# house_rev2.net
KiCad netlist of a schematic drawn in EAGLE
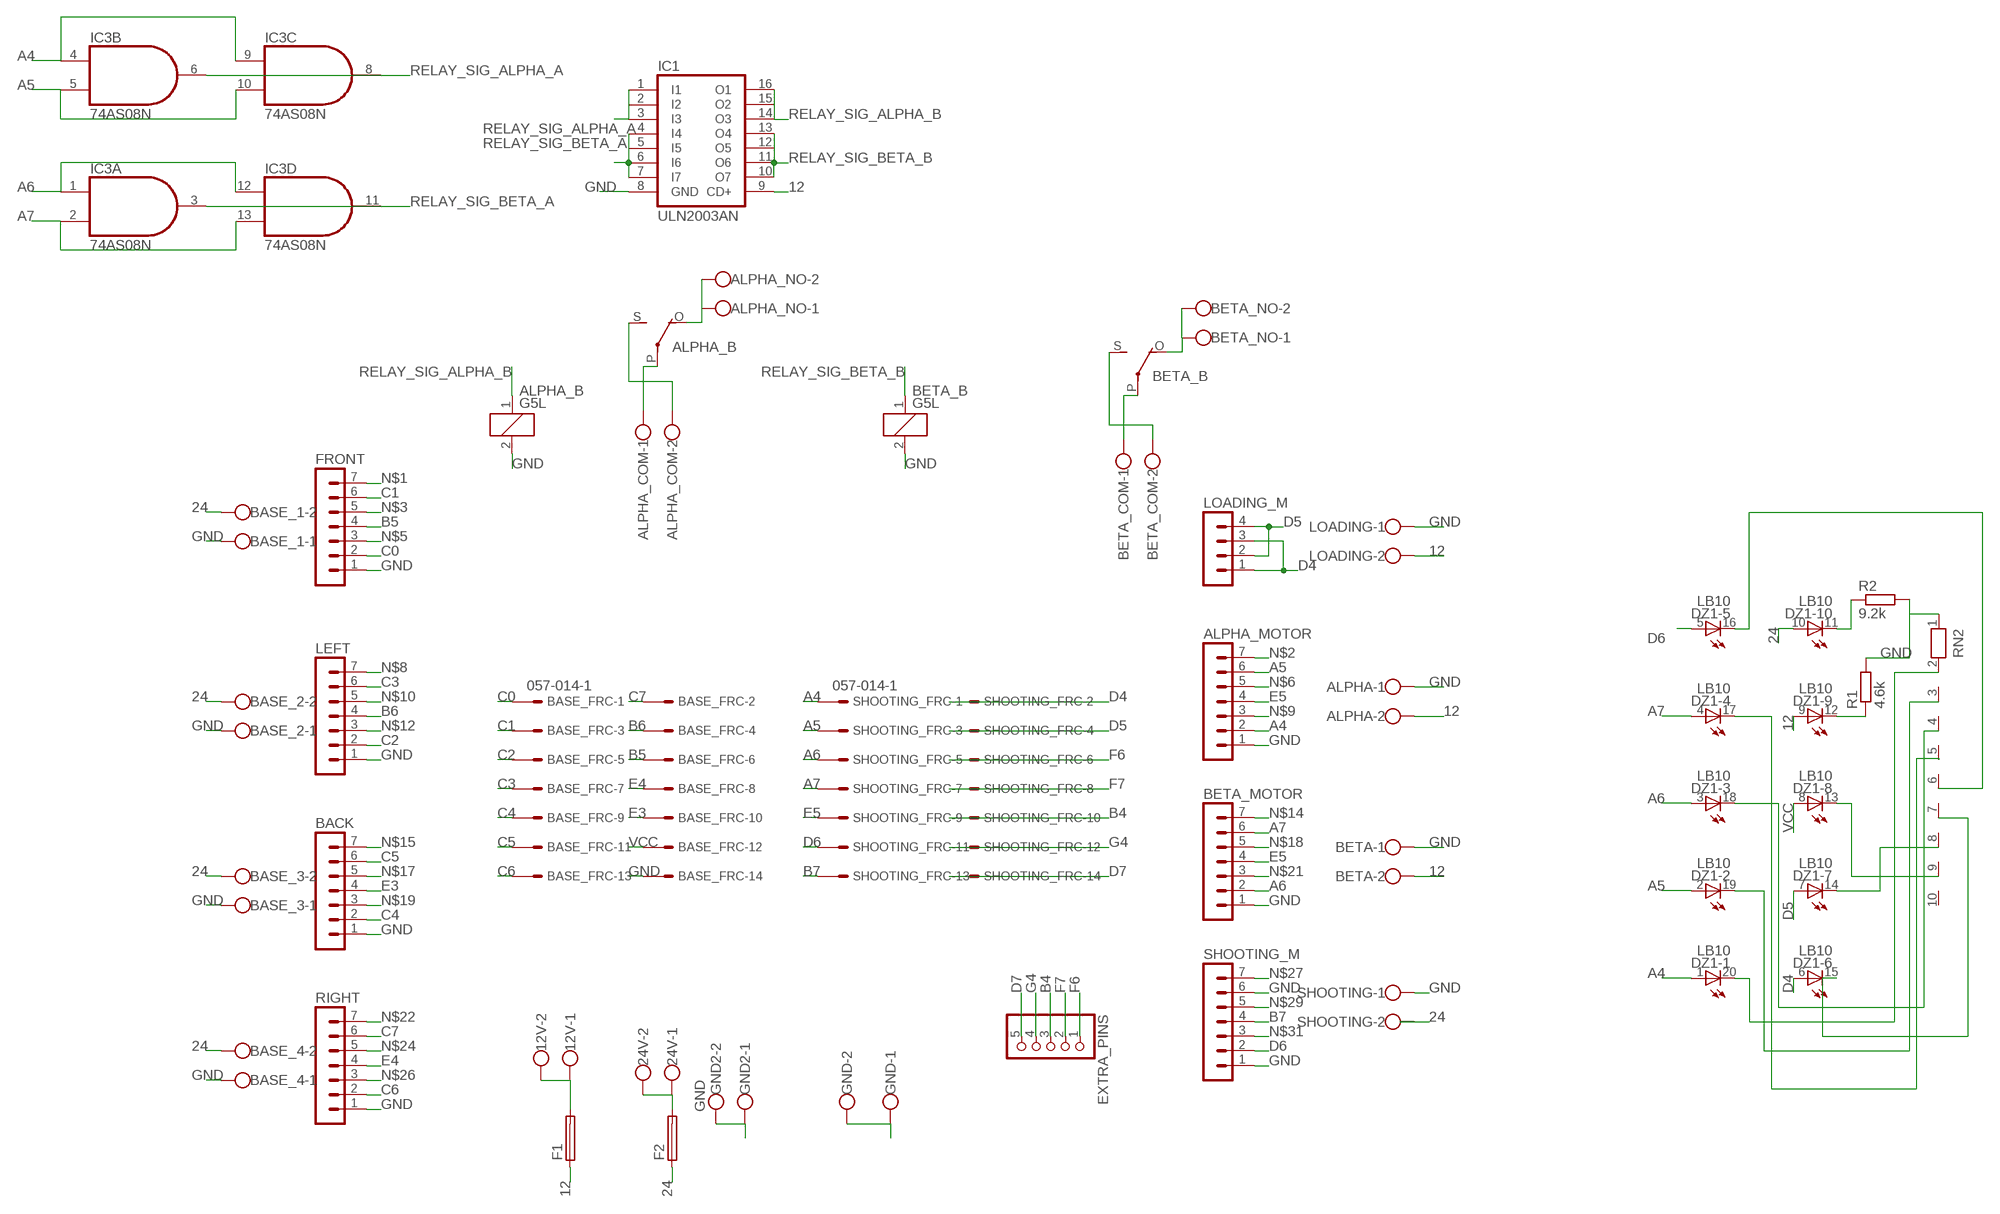
[diagram p0: schematic, sheet 1]

(export (version "E")
  (design (tool "Eeschema 10.0.6"))
  (components
    (comp (ref "12V")
      (value "W237-102")
      (footprint "eagle-import:W237-102")
      (fields (field (name "MPN") "237-102"))
      (libsource (lib "eagle-import") (part "W237-102"))
    )
    (comp (ref "24V")
      (value "W237-102")
      (footprint "eagle-import:W237-102")
      (fields (field (name "MPN") "237-102"))
      (libsource (lib "eagle-import") (part "W237-102"))
    )
    (comp (ref "ALPHA")
      (value "W237-102")
      (footprint "eagle-import:W237-102")
      (fields (field (name "MPN") "237-102"))
      (libsource (lib "eagle-import") (part "W237-102"))
    )
    (comp (ref "ALPHA_B")
      (value "G5L")
      (footprint "eagle-import:G5LE")
      (libsource (lib "eagle-import") (part "G5L"))
    )
    (comp (ref "ALPHA_COM")
      (value "W237-102")
      (footprint "eagle-import:W237-102")
      (fields (field (name "MPN") "237-102"))
      (libsource (lib "eagle-import") (part "W237-102"))
    )
    (comp (ref "ALPHA_MOTOR")
      (value "MA07-1")
      (footprint "eagle-import:MA07-1")
      (libsource (lib "eagle-import") (part "MA07-1"))
    )
    (comp (ref "ALPHA_NO")
      (value "W237-102")
      (footprint "eagle-import:W237-102")
      (fields (field (name "MPN") "237-102"))
      (libsource (lib "eagle-import") (part "W237-102"))
    )
    (comp (ref "BACK")
      (value "MA07-1")
      (footprint "eagle-import:MA07-1")
      (libsource (lib "eagle-import") (part "MA07-1"))
    )
    (comp (ref "BASE_1")
      (value "W237-102")
      (footprint "eagle-import:W237-102")
      (fields (field (name "MPN") "237-102"))
      (libsource (lib "eagle-import") (part "W237-102"))
    )
    (comp (ref "BASE_2")
      (value "W237-102")
      (footprint "eagle-import:W237-102")
      (fields (field (name "MPN") "237-102"))
      (libsource (lib "eagle-import") (part "W237-102"))
    )
    (comp (ref "BASE_3")
      (value "W237-102")
      (footprint "eagle-import:W237-102")
      (fields (field (name "MPN") "237-102"))
      (libsource (lib "eagle-import") (part "W237-102"))
    )
    (comp (ref "BASE_4")
      (value "W237-102")
      (footprint "eagle-import:W237-102")
      (fields (field (name "MPN") "237-102"))
      (libsource (lib "eagle-import") (part "W237-102"))
    )
    (comp (ref "BASE_FRC")
      (value "057-014-1")
      (footprint "eagle-import:057-014-1")
      (libsource (lib "eagle-import") (part "057-014-1"))
    )
    (comp (ref "BETA")
      (value "W237-102")
      (footprint "eagle-import:W237-102")
      (fields (field (name "MPN") "237-102"))
      (libsource (lib "eagle-import") (part "W237-102"))
    )
    (comp (ref "BETA_B")
      (value "G5L")
      (footprint "eagle-import:G5LE")
      (libsource (lib "eagle-import") (part "G5L"))
    )
    (comp (ref "BETA_COM")
      (value "W237-102")
      (footprint "eagle-import:W237-102")
      (fields (field (name "MPN") "237-102"))
      (libsource (lib "eagle-import") (part "W237-102"))
    )
    (comp (ref "BETA_MOTOR")
      (value "MA07-1")
      (footprint "eagle-import:MA07-1")
      (libsource (lib "eagle-import") (part "MA07-1"))
    )
    (comp (ref "BETA_NO")
      (value "W237-102")
      (footprint "eagle-import:W237-102")
      (fields (field (name "MPN") "237-102"))
      (libsource (lib "eagle-import") (part "W237-102"))
    )
    (comp (ref "DZ1")
      (value "LB10")
      (footprint "eagle-import:LB10")
      (libsource (lib "eagle-import") (part "LB10"))
    )
    (comp (ref "EXTRA_PINS")
      (value "PINHD-1X5")
      (footprint "eagle-import:1X05")
      (libsource (lib "eagle-import") (part "PINHD-1X5"))
    )
    (comp (ref "F1")
      (value "SH25")
      (footprint "eagle-import:SH25")
      (fields (field (name "MF") "SCHURTER") (field (name "MPN") "0031.8211"))
      (libsource (lib "eagle-import") (part "SH25"))
    )
    (comp (ref "F2")
      (value "SH25")
      (footprint "eagle-import:SH25")
      (fields (field (name "MF") "SCHURTER") (field (name "MPN") "0031.8211"))
      (libsource (lib "eagle-import") (part "SH25"))
    )
    (comp (ref "FRONT")
      (value "MA07-1")
      (footprint "eagle-import:MA07-1")
      (libsource (lib "eagle-import") (part "MA07-1"))
    )
    (comp (ref "GND")
      (value "W237-102")
      (footprint "eagle-import:W237-102")
      (fields (field (name "MPN") "237-102"))
      (libsource (lib "eagle-import") (part "W237-102"))
    )
    (comp (ref "GND2")
      (value "GND")
      (footprint "eagle-import:W237-102")
      (fields (field (name "MPN") "237-102"))
      (libsource (lib "eagle-import") (part "W237-102"))
    )
    (comp (ref "IC1")
      (value "ULN2003AN")
      (footprint "eagle-import:DIL16")
      (libsource (lib "eagle-import") (part "ULN2003AN"))
    )
    (comp (ref "IC3")
      (value "74AS08N")
      (footprint "eagle-import:DIL14")
      (libsource (lib "eagle-import") (part "7408NAS"))
    )
    (comp (ref "LEFT")
      (value "MA07-1")
      (footprint "eagle-import:MA07-1")
      (libsource (lib "eagle-import") (part "MA07-1"))
    )
    (comp (ref "LOADING")
      (value "W237-102")
      (footprint "eagle-import:W237-102")
      (fields (field (name "MPN") "237-102"))
      (libsource (lib "eagle-import") (part "W237-102"))
    )
    (comp (ref "LOADING_M")
      (value "MA04-1")
      (footprint "eagle-import:MA04-1")
      (libsource (lib "eagle-import") (part "MA04-1"))
    )
    (comp (ref "R1")
      (value "4.6k")
      (footprint "eagle-import:0204_7")
      (libsource (lib "eagle-import") (part "R-EU_0204/7"))
    )
    (comp (ref "R2")
      (value "9.2k")
      (footprint "eagle-import:0204_7")
      (libsource (lib "eagle-import") (part "R-EU_0204/7"))
    )
    (comp (ref "RIGHT")
      (value "MA07-1")
      (footprint "eagle-import:MA07-1")
      (libsource (lib "eagle-import") (part "MA07-1"))
    )
    (comp (ref "RN2")
      (value "RN09")
      (footprint "eagle-import:RN-10")
      (libsource (lib "eagle-import") (part "RN09"))
    )
    (comp (ref "SHOOTING")
      (value "W237-102")
      (footprint "eagle-import:W237-102")
      (fields (field (name "MPN") "237-102"))
      (libsource (lib "eagle-import") (part "W237-102"))
    )
    (comp (ref "SHOOTING_FRC")
      (value "057-014-1")
      (footprint "eagle-import:057-014-1")
      (libsource (lib "eagle-import") (part "057-014-1"))
    )
    (comp (ref "SHOOTING_M")
      (value "MA07-1")
      (footprint "eagle-import:MA07-1")
      (libsource (lib "eagle-import") (part "MA07-1"))
    )
  )
  (nets
    (net (code "1") (name "/12") (class "Default")
      (node (ref "ALPHA") (pin "2") (pinfunction "KL_2") (pintype "passive"))
      (node (ref "BETA") (pin "2") (pinfunction "KL_2") (pintype "passive"))
      (node (ref "DZ1") (pin "9") (pinfunction "A_9") (pintype "passive"))
      (node (ref "F1") (pin "1") (pinfunction "1_1") (pintype "passive"))
      (node (ref "IC1") (pin "9") (pinfunction "CD+_9") (pintype "passive"))
      (node (ref "LOADING") (pin "2") (pinfunction "KL_2") (pintype "passive"))
    )
    (net (code "2") (name "/24") (class "Default")
      (node (ref "BASE_1") (pin "2") (pinfunction "KL_2") (pintype "passive"))
      (node (ref "BASE_2") (pin "2") (pinfunction "KL_2") (pintype "passive"))
      (node (ref "BASE_3") (pin "2") (pinfunction "KL_2") (pintype "passive"))
      (node (ref "BASE_4") (pin "2") (pinfunction "KL_2") (pintype "passive"))
      (node (ref "DZ1") (pin "10") (pinfunction "A_10") (pintype "passive"))
      (node (ref "F2") (pin "1") (pinfunction "1_1") (pintype "passive"))
      (node (ref "SHOOTING") (pin "2") (pinfunction "KL_2") (pintype "passive"))
    )
    (net (code "3") (name "/A4") (class "Default")
      (node (ref "ALPHA_MOTOR") (pin "2") (pinfunction "2_2") (pintype "passive"))
      (node (ref "DZ1") (pin "1") (pinfunction "A_1") (pintype "passive"))
      (node (ref "IC3") (pin "4") (pinfunction "I0_4") (pintype "input"))
      (node (ref "IC3") (pin "9") (pinfunction "I0_9") (pintype "input"))
      (node (ref "SHOOTING_FRC") (pin "1") (pinfunction "S_1") (pintype "passive"))
    )
    (net (code "4") (name "/A5") (class "Default")
      (node (ref "ALPHA_MOTOR") (pin "6") (pinfunction "6_6") (pintype "passive"))
      (node (ref "DZ1") (pin "2") (pinfunction "A_2") (pintype "passive"))
      (node (ref "IC3") (pin "10") (pinfunction "I1_10") (pintype "input"))
      (node (ref "IC3") (pin "5") (pinfunction "I1_5") (pintype "input"))
      (node (ref "SHOOTING_FRC") (pin "3") (pinfunction "S_3") (pintype "passive"))
    )
    (net (code "5") (name "/A6") (class "Default")
      (node (ref "BETA_MOTOR") (pin "2") (pinfunction "2_2") (pintype "passive"))
      (node (ref "DZ1") (pin "3") (pinfunction "A_3") (pintype "passive"))
      (node (ref "IC3") (pin "1") (pinfunction "I0_1") (pintype "input"))
      (node (ref "IC3") (pin "12") (pinfunction "I0_12") (pintype "input"))
      (node (ref "SHOOTING_FRC") (pin "5") (pinfunction "S_5") (pintype "passive"))
    )
    (net (code "6") (name "/A7") (class "Default")
      (node (ref "BETA_MOTOR") (pin "6") (pinfunction "6_6") (pintype "passive"))
      (node (ref "DZ1") (pin "4") (pinfunction "A_4") (pintype "passive"))
      (node (ref "IC3") (pin "13") (pinfunction "I1_13") (pintype "input"))
      (node (ref "IC3") (pin "2") (pinfunction "I1_2") (pintype "input"))
      (node (ref "SHOOTING_FRC") (pin "7") (pinfunction "S_7") (pintype "passive"))
    )
    (net (code "7") (name "/B4") (class "Default")
      (node (ref "EXTRA_PINS") (pin "3") (pinfunction "3_3") (pintype "passive"))
      (node (ref "SHOOTING_FRC") (pin "10") (pinfunction "S_10") (pintype "passive"))
    )
    (net (code "8") (name "/B5") (class "Default")
      (node (ref "BASE_FRC") (pin "6") (pinfunction "S_6") (pintype "passive"))
      (node (ref "FRONT") (pin "4") (pinfunction "4_4") (pintype "passive"))
    )
    (net (code "9") (name "/B6") (class "Default")
      (node (ref "BASE_FRC") (pin "4") (pinfunction "S_4") (pintype "passive"))
      (node (ref "LEFT") (pin "4") (pinfunction "4_4") (pintype "passive"))
    )
    (net (code "10") (name "/B7") (class "Default")
      (node (ref "SHOOTING_FRC") (pin "13") (pinfunction "S_13") (pintype "passive"))
      (node (ref "SHOOTING_M") (pin "4") (pinfunction "4_4") (pintype "passive"))
    )
    (net (code "11") (name "/C0") (class "Default")
      (node (ref "BASE_FRC") (pin "1") (pinfunction "S_1") (pintype "passive"))
      (node (ref "FRONT") (pin "2") (pinfunction "2_2") (pintype "passive"))
    )
    (net (code "12") (name "/C1") (class "Default")
      (node (ref "BASE_FRC") (pin "3") (pinfunction "S_3") (pintype "passive"))
      (node (ref "FRONT") (pin "6") (pinfunction "6_6") (pintype "passive"))
    )
    (net (code "13") (name "/C2") (class "Default")
      (node (ref "BASE_FRC") (pin "5") (pinfunction "S_5") (pintype "passive"))
      (node (ref "LEFT") (pin "2") (pinfunction "2_2") (pintype "passive"))
    )
    (net (code "14") (name "/C3") (class "Default")
      (node (ref "BASE_FRC") (pin "7") (pinfunction "S_7") (pintype "passive"))
      (node (ref "LEFT") (pin "6") (pinfunction "6_6") (pintype "passive"))
    )
    (net (code "15") (name "/C4") (class "Default")
      (node (ref "BACK") (pin "2") (pinfunction "2_2") (pintype "passive"))
      (node (ref "BASE_FRC") (pin "9") (pinfunction "S_9") (pintype "passive"))
    )
    (net (code "16") (name "/C5") (class "Default")
      (node (ref "BACK") (pin "6") (pinfunction "6_6") (pintype "passive"))
      (node (ref "BASE_FRC") (pin "11") (pinfunction "S_11") (pintype "passive"))
    )
    (net (code "17") (name "/C6") (class "Default")
      (node (ref "BASE_FRC") (pin "13") (pinfunction "S_13") (pintype "passive"))
      (node (ref "RIGHT") (pin "2") (pinfunction "2_2") (pintype "passive"))
    )
    (net (code "18") (name "/C7") (class "Default")
      (node (ref "BASE_FRC") (pin "2") (pinfunction "S_2") (pintype "passive"))
      (node (ref "RIGHT") (pin "6") (pinfunction "6_6") (pintype "passive"))
    )
    (net (code "19") (name "/D4") (class "Default")
      (node (ref "DZ1") (pin "6") (pinfunction "A_6") (pintype "passive"))
      (node (ref "LOADING_M") (pin "1") (pinfunction "1_1") (pintype "passive"))
      (node (ref "LOADING_M") (pin "3") (pinfunction "3_3") (pintype "passive"))
      (node (ref "SHOOTING_FRC") (pin "2") (pinfunction "S_2") (pintype "passive"))
    )
    (net (code "20") (name "/D5") (class "Default")
      (node (ref "DZ1") (pin "7") (pinfunction "A_7") (pintype "passive"))
      (node (ref "LOADING_M") (pin "2") (pinfunction "2_2") (pintype "passive"))
      (node (ref "LOADING_M") (pin "4") (pinfunction "4_4") (pintype "passive"))
      (node (ref "SHOOTING_FRC") (pin "4") (pinfunction "S_4") (pintype "passive"))
    )
    (net (code "21") (name "/D6") (class "Default")
      (node (ref "DZ1") (pin "5") (pinfunction "A_5") (pintype "passive"))
      (node (ref "SHOOTING_FRC") (pin "11") (pinfunction "S_11") (pintype "passive"))
      (node (ref "SHOOTING_M") (pin "2") (pinfunction "2_2") (pintype "passive"))
    )
    (net (code "22") (name "/D7") (class "Default")
      (node (ref "EXTRA_PINS") (pin "5") (pinfunction "5_5") (pintype "passive"))
      (node (ref "SHOOTING_FRC") (pin "14") (pinfunction "S_14") (pintype "passive"))
    )
    (net (code "23") (name "/E3") (class "Default")
      (node (ref "BACK") (pin "4") (pinfunction "4_4") (pintype "passive"))
      (node (ref "BASE_FRC") (pin "10") (pinfunction "S_10") (pintype "passive"))
    )
    (net (code "24") (name "/E4") (class "Default")
      (node (ref "BASE_FRC") (pin "8") (pinfunction "S_8") (pintype "passive"))
      (node (ref "RIGHT") (pin "4") (pinfunction "4_4") (pintype "passive"))
    )
    (net (code "25") (name "/E5") (class "Default")
      (node (ref "ALPHA_MOTOR") (pin "4") (pinfunction "4_4") (pintype "passive"))
      (node (ref "BETA_MOTOR") (pin "4") (pinfunction "4_4") (pintype "passive"))
      (node (ref "SHOOTING_FRC") (pin "9") (pinfunction "S_9") (pintype "passive"))
    )
    (net (code "26") (name "/F6") (class "Default")
      (node (ref "EXTRA_PINS") (pin "1") (pinfunction "1_1") (pintype "passive"))
      (node (ref "SHOOTING_FRC") (pin "6") (pinfunction "S_6") (pintype "passive"))
    )
    (net (code "27") (name "/F7") (class "Default")
      (node (ref "EXTRA_PINS") (pin "2") (pinfunction "2_2") (pintype "passive"))
      (node (ref "SHOOTING_FRC") (pin "8") (pinfunction "S_8") (pintype "passive"))
    )
    (net (code "28") (name "/G4") (class "Default")
      (node (ref "EXTRA_PINS") (pin "4") (pinfunction "4_4") (pintype "passive"))
      (node (ref "SHOOTING_FRC") (pin "12") (pinfunction "S_12") (pintype "passive"))
    )
    (net (code "29") (name "/GND") (class "Default")
      (node (ref "ALPHA") (pin "1") (pinfunction "KL_1") (pintype "passive"))
      (node (ref "ALPHA_B") (pin "2") (pinfunction "2_2") (pintype "passive"))
      (node (ref "ALPHA_MOTOR") (pin "1") (pinfunction "1_1") (pintype "passive"))
      (node (ref "BACK") (pin "1") (pinfunction "1_1") (pintype "passive"))
      (node (ref "BASE_1") (pin "1") (pinfunction "KL_1") (pintype "passive"))
      (node (ref "BASE_2") (pin "1") (pinfunction "KL_1") (pintype "passive"))
      (node (ref "BASE_3") (pin "1") (pinfunction "KL_1") (pintype "passive"))
      (node (ref "BASE_4") (pin "1") (pinfunction "KL_1") (pintype "passive"))
      (node (ref "BASE_FRC") (pin "14") (pinfunction "S_14") (pintype "passive"))
      (node (ref "BETA") (pin "1") (pinfunction "KL_1") (pintype "passive"))
      (node (ref "BETA_B") (pin "2") (pinfunction "2_2") (pintype "passive"))
      (node (ref "BETA_MOTOR") (pin "1") (pinfunction "1_1") (pintype "passive"))
      (node (ref "FRONT") (pin "1") (pinfunction "1_1") (pintype "passive"))
      (node (ref "GND") (pin "1") (pinfunction "KL_1") (pintype "passive"))
      (node (ref "GND") (pin "2") (pinfunction "KL_2") (pintype "passive"))
      (node (ref "GND2") (pin "1") (pinfunction "KL_1") (pintype "passive"))
      (node (ref "GND2") (pin "2") (pinfunction "KL_2") (pintype "passive"))
      (node (ref "IC1") (pin "8") (pinfunction "GND_8") (pintype "power_in"))
      (node (ref "LEFT") (pin "1") (pinfunction "1_1") (pintype "passive"))
      (node (ref "LOADING") (pin "1") (pinfunction "KL_1") (pintype "passive"))
      (node (ref "R1") (pin "2") (pinfunction "2_2") (pintype "passive"))
      (node (ref "R2") (pin "2") (pinfunction "2_2") (pintype "passive"))
      (node (ref "RIGHT") (pin "1") (pinfunction "1_1") (pintype "passive"))
      (node (ref "RN2") (pin "1") (pinfunction "1_1") (pintype "passive"))
      (node (ref "SHOOTING") (pin "1") (pinfunction "KL_1") (pintype "passive"))
      (node (ref "SHOOTING_M") (pin "1") (pinfunction "1_1") (pintype "passive"))
      (node (ref "SHOOTING_M") (pin "6") (pinfunction "6_6") (pintype "passive"))
    )
    (net (code "30") (name "/N$1") (class "Default")
      (node (ref "FRONT") (pin "7") (pinfunction "7_7") (pintype "passive"))
    )
    (net (code "31") (name "/N$2") (class "Default")
      (node (ref "ALPHA_MOTOR") (pin "7") (pinfunction "7_7") (pintype "passive"))
    )
    (net (code "32") (name "/N$3") (class "Default")
      (node (ref "FRONT") (pin "5") (pinfunction "5_5") (pintype "passive"))
    )
    (net (code "33") (name "/N$5") (class "Default")
      (node (ref "FRONT") (pin "3") (pinfunction "3_3") (pintype "passive"))
    )
    (net (code "34") (name "/N$6") (class "Default")
      (node (ref "ALPHA_MOTOR") (pin "5") (pinfunction "5_5") (pintype "passive"))
    )
    (net (code "35") (name "/N$8") (class "Default")
      (node (ref "LEFT") (pin "7") (pinfunction "7_7") (pintype "passive"))
    )
    (net (code "36") (name "/N$9") (class "Default")
      (node (ref "ALPHA_MOTOR") (pin "3") (pinfunction "3_3") (pintype "passive"))
    )
    (net (code "37") (name "/N$10") (class "Default")
      (node (ref "LEFT") (pin "5") (pinfunction "5_5") (pintype "passive"))
    )
    (net (code "38") (name "/N$12") (class "Default")
      (node (ref "LEFT") (pin "3") (pinfunction "3_3") (pintype "passive"))
    )
    (net (code "39") (name "/N$14") (class "Default")
      (node (ref "BETA_MOTOR") (pin "7") (pinfunction "7_7") (pintype "passive"))
    )
    (net (code "40") (name "/N$15") (class "Default")
      (node (ref "BACK") (pin "7") (pinfunction "7_7") (pintype "passive"))
    )
    (net (code "41") (name "/N$17") (class "Default")
      (node (ref "BACK") (pin "5") (pinfunction "5_5") (pintype "passive"))
    )
    (net (code "42") (name "/N$18") (class "Default")
      (node (ref "BETA_MOTOR") (pin "5") (pinfunction "5_5") (pintype "passive"))
    )
    (net (code "43") (name "/N$19") (class "Default")
      (node (ref "BACK") (pin "3") (pinfunction "3_3") (pintype "passive"))
    )
    (net (code "44") (name "/N$21") (class "Default")
      (node (ref "BETA_MOTOR") (pin "3") (pinfunction "3_3") (pintype "passive"))
    )
    (net (code "45") (name "/N$22") (class "Default")
      (node (ref "RIGHT") (pin "7") (pinfunction "7_7") (pintype "passive"))
    )
    (net (code "46") (name "/N$24") (class "Default")
      (node (ref "RIGHT") (pin "5") (pinfunction "5_5") (pintype "passive"))
    )
    (net (code "47") (name "/N$26") (class "Default")
      (node (ref "RIGHT") (pin "3") (pinfunction "3_3") (pintype "passive"))
    )
    (net (code "48") (name "/N$27") (class "Default")
      (node (ref "SHOOTING_M") (pin "7") (pinfunction "7_7") (pintype "passive"))
    )
    (net (code "49") (name "/N$29") (class "Default")
      (node (ref "SHOOTING_M") (pin "5") (pinfunction "5_5") (pintype "passive"))
    )
    (net (code "50") (name "/N$31") (class "Default")
      (node (ref "SHOOTING_M") (pin "3") (pinfunction "3_3") (pintype "passive"))
    )
    (net (code "51") (name "/RELAY_SIG_ALPHA_A") (class "Default")
      (node (ref "IC1") (pin "1") (pinfunction "I1_1") (pintype "input"))
      (node (ref "IC1") (pin "2") (pinfunction "I2_2") (pintype "input"))
      (node (ref "IC1") (pin "3") (pinfunction "I3_3") (pintype "input"))
      (node (ref "IC3") (pin "6") (pinfunction "O_6") (pintype "output"))
      (node (ref "IC3") (pin "8") (pinfunction "O_8") (pintype "output"))
    )
    (net (code "52") (name "/RELAY_SIG_ALPHA_B") (class "Default")
      (node (ref "ALPHA_B") (pin "1") (pinfunction "1_1") (pintype "passive"))
      (node (ref "IC1") (pin "14") (pinfunction "O3_14") (pintype "open_collector"))
      (node (ref "IC1") (pin "15") (pinfunction "O2_15") (pintype "open_collector"))
      (node (ref "IC1") (pin "16") (pinfunction "O1_16") (pintype "open_collector"))
    )
    (net (code "53") (name "/RELAY_SIG_BETA_A") (class "Default")
      (node (ref "IC1") (pin "4") (pinfunction "I4_4") (pintype "input"))
      (node (ref "IC1") (pin "5") (pinfunction "I5_5") (pintype "input"))
      (node (ref "IC1") (pin "6") (pinfunction "I6_6") (pintype "input"))
      (node (ref "IC1") (pin "7") (pinfunction "I7_7") (pintype "input"))
      (node (ref "IC3") (pin "11") (pinfunction "O_11") (pintype "output"))
      (node (ref "IC3") (pin "3") (pinfunction "O_3") (pintype "output"))
    )
    (net (code "54") (name "/RELAY_SIG_BETA_B") (class "Default")
      (node (ref "BETA_B") (pin "1") (pinfunction "1_1") (pintype "passive"))
      (node (ref "IC1") (pin "10") (pinfunction "O7_10") (pintype "open_collector"))
      (node (ref "IC1") (pin "11") (pinfunction "O6_11") (pintype "open_collector"))
      (node (ref "IC1") (pin "12") (pinfunction "O5_12") (pintype "open_collector"))
      (node (ref "IC1") (pin "13") (pinfunction "O4_13") (pintype "open_collector"))
    )
    (net (code "55") (name "/VCC") (class "Default")
      (node (ref "BASE_FRC") (pin "12") (pinfunction "S_12") (pintype "passive"))
      (node (ref "DZ1") (pin "8") (pinfunction "A_8") (pintype "passive"))
    )
    (net (code "56") (name "Net-(12VA-KL)") (class "Default")
      (node (ref "12V") (pin "1") (pinfunction "KL_1") (pintype "passive"))
      (node (ref "12V") (pin "2") (pinfunction "KL_2") (pintype "passive"))
      (node (ref "F1") (pin "2") (pinfunction "2_2") (pintype "passive"))
    )
    (net (code "57") (name "Net-(24VA-KL)") (class "Default")
      (node (ref "24V") (pin "1") (pinfunction "KL_1") (pintype "passive"))
      (node (ref "24V") (pin "2") (pinfunction "KL_2") (pintype "passive"))
      (node (ref "F2") (pin "2") (pinfunction "2_2") (pintype "passive"))
    )
    (net (code "58") (name "Net-(ALPHA_COMA-KL)") (class "Default")
      (node (ref "ALPHA_B") (pin "P") (pinfunction "P_P") (pintype "passive"))
      (node (ref "ALPHA_COM") (pin "1") (pinfunction "KL_1") (pintype "passive"))
    )
    (net (code "59") (name "Net-(ALPHA_COMB-KL)") (class "Default")
      (node (ref "ALPHA_B") (pin "S") (pinfunction "S_S") (pintype "passive"))
      (node (ref "ALPHA_COM") (pin "2") (pinfunction "KL_2") (pintype "passive"))
    )
    (net (code "60") (name "Net-(ALPHA_NOA-KL)") (class "Default")
      (node (ref "ALPHA_B") (pin "O") (pinfunction "O_O") (pintype "passive"))
      (node (ref "ALPHA_NO") (pin "1") (pinfunction "KL_1") (pintype "passive"))
      (node (ref "ALPHA_NO") (pin "2") (pinfunction "KL_2") (pintype "passive"))
    )
    (net (code "61") (name "Net-(BETA_COMA-KL)") (class "Default")
      (node (ref "BETA_B") (pin "P") (pinfunction "P_P") (pintype "passive"))
      (node (ref "BETA_COM") (pin "1") (pinfunction "KL_1") (pintype "passive"))
    )
    (net (code "62") (name "Net-(BETA_COMB-KL)") (class "Default")
      (node (ref "BETA_B") (pin "S") (pinfunction "S_S") (pintype "passive"))
      (node (ref "BETA_COM") (pin "2") (pinfunction "KL_2") (pintype "passive"))
    )
    (net (code "63") (name "Net-(BETA_NOA-KL)") (class "Default")
      (node (ref "BETA_B") (pin "O") (pinfunction "O_O") (pintype "passive"))
      (node (ref "BETA_NO") (pin "1") (pinfunction "KL_1") (pintype "passive"))
      (node (ref "BETA_NO") (pin "2") (pinfunction "KL_2") (pintype "passive"))
    )
    (net (code "64") (name "Net-(DZ1A-C)") (class "Default")
      (node (ref "DZ1") (pin "20") (pinfunction "C_20") (pintype "passive"))
      (node (ref "RN2") (pin "2") (pinfunction "2_2") (pintype "passive"))
    )
    (net (code "65") (name "Net-(DZ1B-C)") (class "Default")
      (node (ref "DZ1") (pin "11") (pinfunction "C_11") (pintype "passive"))
      (node (ref "R2") (pin "1") (pinfunction "1_1") (pintype "passive"))
    )
    (net (code "66") (name "Net-(DZ1C-C)") (class "Default")
      (node (ref "DZ1") (pin "19") (pinfunction "C_19") (pintype "passive"))
      (node (ref "RN2") (pin "3") (pinfunction "3_3") (pintype "passive"))
    )
    (net (code "67") (name "Net-(DZ1D-C)") (class "Default")
      (node (ref "DZ1") (pin "18") (pinfunction "C_18") (pintype "passive"))
      (node (ref "RN2") (pin "4") (pinfunction "4_4") (pintype "passive"))
    )
    (net (code "68") (name "Net-(DZ1E-C)") (class "Default")
      (node (ref "DZ1") (pin "17") (pinfunction "C_17") (pintype "passive"))
      (node (ref "RN2") (pin "5") (pinfunction "5_5") (pintype "passive"))
    )
    (net (code "69") (name "Net-(DZ1F-C)") (class "Default")
      (node (ref "DZ1") (pin "16") (pinfunction "C_16") (pintype "passive"))
      (node (ref "RN2") (pin "6") (pinfunction "6_6") (pintype "passive"))
    )
    (net (code "70") (name "Net-(DZ1G-C)") (class "Default")
      (node (ref "DZ1") (pin "15") (pinfunction "C_15") (pintype "passive"))
      (node (ref "RN2") (pin "7") (pinfunction "7_7") (pintype "passive"))
    )
    (net (code "71") (name "Net-(DZ1H-C)") (class "Default")
      (node (ref "DZ1") (pin "14") (pinfunction "C_14") (pintype "passive"))
      (node (ref "RN2") (pin "8") (pinfunction "8_8") (pintype "passive"))
    )
    (net (code "72") (name "Net-(DZ1I-C)") (class "Default")
      (node (ref "DZ1") (pin "13") (pinfunction "C_13") (pintype "passive"))
      (node (ref "RN2") (pin "9") (pinfunction "9_9") (pintype "passive"))
    )
    (net (code "73") (name "Net-(DZ1J-C)") (class "Default")
      (node (ref "DZ1") (pin "12") (pinfunction "C_12") (pintype "passive"))
      (node (ref "R1") (pin "1") (pinfunction "1_1") (pintype "passive"))
    )
    (net (code "74") (name "unconnected-(RN2-Pad10)") (class "Default")
      (node (ref "RN2") (pin "10") (pinfunction "10_10") (pintype "passive"))
    )
  )
)
